# Connectors.net
KiCad netlist of a schematic drawn in Altium Designer
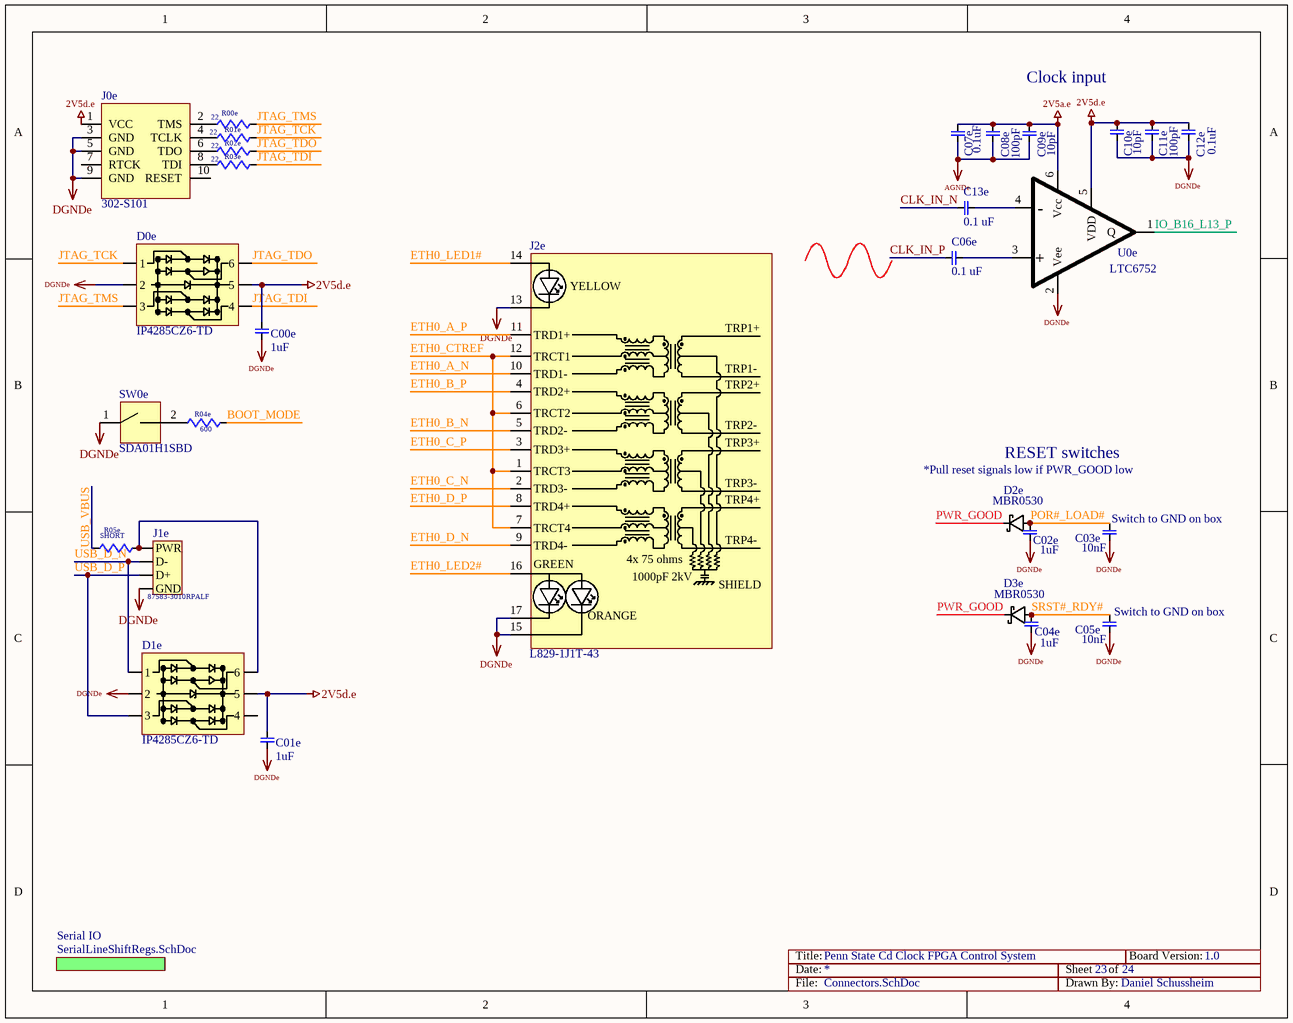
[diagram p0: Connectors.SchDoc]

(export (version "E")
  (design (tool "Eeschema 10.0.6"))
  (components
    (comp (ref "C00e")
      (value "1uF")
      (footprint "0603")
      (libsource (lib "Mercury_AD_BaseBoard_SCHLIB") (part "CAP"))
    )
    (comp (ref "C01e")
      (value "1uF")
      (footprint "0603")
      (libsource (lib "Mercury_AD_BaseBoard_SCHLIB") (part "CAP"))
    )
    (comp (ref "C02e")
      (value "1uF")
      (footprint "0603")
      (libsource (lib "Mercury_AD_BaseBoard_SCHLIB") (part "CAP"))
    )
    (comp (ref "C03e")
      (value "10nF")
      (footprint "0603")
      (libsource (lib "Mercury_AD_BaseBoard_SCHLIB") (part "CAP"))
    )
    (comp (ref "C04e")
      (value "1uF")
      (footprint "0603")
      (libsource (lib "Mercury_AD_BaseBoard_SCHLIB") (part "CAP"))
    )
    (comp (ref "C05e")
      (value "10nF")
      (footprint "0603")
      (libsource (lib "Mercury_AD_BaseBoard_SCHLIB") (part "CAP"))
    )
    (comp (ref "C06e") (value "0.1 uF") (footprint "0805") (libsource (lib "") (part "CAP_1")))
    (comp (ref "C07e")
      (value "0.1uF")
      (footprint "0603")
      (libsource (lib "Mercury_AD_BaseBoard_SCHLIB") (part "CAP"))
    )
    (comp (ref "C08e")
      (value "100pF")
      (footprint "0603")
      (libsource (lib "Mercury_AD_BaseBoard_SCHLIB") (part "CAP"))
    )
    (comp (ref "C09e")
      (value "10pF")
      (footprint "0603")
      (libsource (lib "Mercury_AD_BaseBoard_SCHLIB") (part "CAP"))
    )
    (comp (ref "C10e")
      (value "10pF")
      (footprint "0603")
      (libsource (lib "Mercury_AD_BaseBoard_SCHLIB") (part "CAP"))
    )
    (comp (ref "C11e")
      (value "100pF")
      (footprint "0603")
      (libsource (lib "Mercury_AD_BaseBoard_SCHLIB") (part "CAP"))
    )
    (comp (ref "C12e")
      (value "0.1uF")
      (footprint "0603")
      (libsource (lib "Mercury_AD_BaseBoard_SCHLIB") (part "CAP"))
    )
    (comp (ref "C13e") (value "0.1 uF") (footprint "0805") (libsource (lib "") (part "CAP_1")))
    (comp (ref "D0e")
      (value "IP4285CZ6-TD")
      (footprint "6-TSOP")
      (libsource (lib "Mercury_AD_BaseBoard_SCHLIB") (part "IP4285CZ6-TD"))
    )
    (comp (ref "D1e")
      (value "IP4285CZ6-TD")
      (footprint "6-TSOP")
      (libsource (lib "Mercury_AD_BaseBoard_SCHLIB") (part "IP4285CZ6-TD"))
    )
    (comp (ref "D2e")
      (value "MBR0530")
      (footprint "SOD123")
      (libsource (lib "Mercury_AD_BaseBoard_SCHLIB") (part "Schottky_Diode"))
    )
    (comp (ref "D3e")
      (value "MBR0530")
      (footprint "SOD123")
      (libsource (lib "Mercury_AD_BaseBoard_SCHLIB") (part "Schottky_Diode"))
    )
    (comp (ref "J0e")
      (value "302-S101")
      (footprint "3020-10-0300-00")
      (description "JTAG Connector")
      (libsource (lib "Mercury_AD_BaseBoard_SCHLIB") (part "JTAG_10"))
    )
    (comp (ref "J1e")
      (value "87583-3010RPALF")
      (footprint "87583-3010RPALF")
      (libsource (lib "Mercury_AD_BaseBoard_SCHLIB") (part "87583-3010RPALF"))
    )
    (comp (ref "J2e")
      (value "L829-1J1T-43")
      (footprint "L829-1J1T-43")
      (libsource (lib "Mercury_AD_BaseBoard_SCHLIB") (part "L829-1J1T-43"))
    )
    (comp (ref "R00e")
      (value "22")
      (footprint "0603")
      (libsource (lib "Mercury_AD_BaseBoard_SCHLIB") (part "RES"))
    )
    (comp (ref "R01e")
      (value "22")
      (footprint "0603")
      (libsource (lib "Mercury_AD_BaseBoard_SCHLIB") (part "RES"))
    )
    (comp (ref "R02e")
      (value "22")
      (footprint "0603")
      (libsource (lib "Mercury_AD_BaseBoard_SCHLIB") (part "RES"))
    )
    (comp (ref "R03e")
      (value "22")
      (footprint "0603")
      (libsource (lib "Mercury_AD_BaseBoard_SCHLIB") (part "RES"))
    )
    (comp (ref "R04e")
      (value "600")
      (footprint "0603")
      (libsource (lib "Mercury_AD_BaseBoard_SCHLIB") (part "RES"))
    )
    (comp (ref "R05e")
      (value "SHORT")
      (footprint "0603")
      (libsource (lib "Mercury_AD_BaseBoard_SCHLIB") (part "RES"))
    )
    (comp (ref "SW0e")
      (value "SDA01H1SBD")
      (footprint "SDA01H1SBD")
      (libsource (lib "Mercury_AD_BaseBoard_SCHLIB") (part "SW1"))
    )
    (comp (ref "U0e")
      (value "LTC6752")
      (footprint "sc70")
      (libsource (lib "Mercury_AD_BaseBoard_SCHLIB") (part "LTC6752"))
    )
  )
  (nets
    (net (code "1") (name "/BOOT_MODE") (class "Default") (node (ref "R04e") (pin "2") (pintype "passive")))
    (net (code "2") (name "/CLK_IN_N") (class "Default") (node (ref "C13e") (pin "1") (pintype "passive")))
    (net (code "3") (name "/CLK_IN_P") (class "Default") (node (ref "C06e") (pin "1") (pintype "passive")))
    (net (code "4") (name "/ETH0_A_N") (class "Default")
      (node (ref "J2e") (pin "10") (pinfunction "TRD1-_10") (pintype "passive"))
    )
    (net (code "5") (name "/ETH0_A_P") (class "Default")
      (node (ref "J2e") (pin "11") (pinfunction "TRD1+_11") (pintype "passive"))
    )
    (net (code "6") (name "/ETH0_B_N") (class "Default")
      (node (ref "J2e") (pin "5") (pinfunction "TRD2-_5") (pintype "passive"))
    )
    (net (code "7") (name "/ETH0_B_P") (class "Default")
      (node (ref "J2e") (pin "4") (pinfunction "TRD2+_4") (pintype "passive"))
    )
    (net (code "8") (name "/ETH0_CTREF") (class "Default")
      (node (ref "J2e") (pin "1") (pinfunction "TRCT3_1") (pintype "passive"))
      (node (ref "J2e") (pin "12") (pinfunction "TRCT1_12") (pintype "passive"))
      (node (ref "J2e") (pin "6") (pinfunction "TRCT2_6") (pintype "passive"))
      (node (ref "J2e") (pin "7") (pinfunction "TRCT4_7") (pintype "passive"))
    )
    (net (code "9") (name "/ETH0_C_N") (class "Default")
      (node (ref "J2e") (pin "2") (pinfunction "TRD3-_2") (pintype "passive"))
    )
    (net (code "10") (name "/ETH0_C_P") (class "Default")
      (node (ref "J2e") (pin "3") (pinfunction "TRD3+_3") (pintype "passive"))
    )
    (net (code "11") (name "/ETH0_D_N") (class "Default")
      (node (ref "J2e") (pin "9") (pinfunction "TRD4-_9") (pintype "passive"))
    )
    (net (code "12") (name "/ETH0_D_P") (class "Default")
      (node (ref "J2e") (pin "8") (pinfunction "TRD4+_8") (pintype "passive"))
    )
    (net (code "13") (name "/ETH0_LED1#") (class "Default") (node (ref "J2e") (pin "14") (pintype "passive")))
    (net (code "14") (name "/ETH0_LED2#") (class "Default") (node (ref "J2e") (pin "16") (pintype "passive")))
    (net (code "15") (name "/IO_B16_L13_P") (class "Default")
      (node (ref "U0e") (pin "1") (pinfunction "Q_1") (pintype "passive"))
    )
    (net (code "16") (name "/JTAG_TCK") (class "Default")
      (node (ref "D0e") (pin "1") (pinfunction "1_1") (pintype "passive"))
      (node (ref "R01e") (pin "2") (pintype "passive"))
    )
    (net (code "17") (name "/JTAG_TDI") (class "Default")
      (node (ref "D0e") (pin "4") (pinfunction "4_4") (pintype "passive"))
      (node (ref "R03e") (pin "2") (pintype "passive"))
    )
    (net (code "18") (name "/JTAG_TDO") (class "Default")
      (node (ref "D0e") (pin "6") (pinfunction "6_6") (pintype "passive"))
      (node (ref "R02e") (pin "2") (pintype "passive"))
    )
    (net (code "19") (name "/JTAG_TMS") (class "Default")
      (node (ref "D0e") (pin "3") (pinfunction "3_3") (pintype "passive"))
      (node (ref "R00e") (pin "1") (pintype "passive"))
    )
    (net (code "20") (name "/POR#_LOAD#") (class "Default")
      (node (ref "C02e") (pin "1") (pintype "passive"))
      (node (ref "C03e") (pin "1") (pintype "passive"))
      (node (ref "D2e") (pin "2") (pinfunction "2_2") (pintype "passive"))
    )
    (net (code "21") (name "/PWR_GOOD") (class "Default")
      (node (ref "D2e") (pin "1") (pinfunction "1_1") (pintype "passive"))
      (node (ref "D3e") (pin "1") (pinfunction "1_1") (pintype "passive"))
    )
    (net (code "22") (name "/SRST#_RDY#") (class "Default")
      (node (ref "C04e") (pin "1") (pintype "passive"))
      (node (ref "C05e") (pin "1") (pintype "passive"))
      (node (ref "D3e") (pin "2") (pinfunction "2_2") (pintype "passive"))
    )
    (net (code "23") (name "/USB_D_N") (class "Default")
      (node (ref "D1e") (pin "1") (pinfunction "1_1") (pintype "passive"))
      (node (ref "J1e") (pin "D-") (pinfunction "D-_D-") (pintype "passive"))
    )
    (net (code "24") (name "/USB_D_P") (class "Default")
      (node (ref "D1e") (pin "3") (pinfunction "3_3") (pintype "passive"))
      (node (ref "J1e") (pin "D+") (pinfunction "D+_D+") (pintype "passive"))
    )
    (net (code "25") (name "/USB_VBUS") (class "Default") (node (ref "R05e") (pin "1") (pintype "passive")))
    (net (code "26") (name "2V5a.e") (class "Default")
      (node (ref "C07e") (pin "1") (pintype "passive"))
      (node (ref "C08e") (pin "1") (pintype "passive"))
      (node (ref "C09e") (pin "1") (pintype "passive"))
      (node (ref "U0e") (pin "6") (pinfunction "Vcc_6") (pintype "passive"))
    )
    (net (code "27") (name "2V5d.e") (class "Default")
      (node (ref "C00e") (pin "1") (pintype "passive"))
      (node (ref "C01e") (pin "1") (pintype "passive"))
      (node (ref "C10e") (pin "1") (pintype "passive"))
      (node (ref "C11e") (pin "1") (pintype "passive"))
      (node (ref "C12e") (pin "1") (pintype "passive"))
      (node (ref "D0e") (pin "5") (pinfunction "5_5") (pintype "passive"))
      (node (ref "D1e") (pin "5") (pinfunction "5_5") (pintype "passive"))
      (node (ref "J0e") (pin "1") (pinfunction "VCC_1") (pintype "passive"))
      (node (ref "U0e") (pin "5") (pinfunction "VDD_5") (pintype "passive"))
    )
    (net (code "28") (name "AGNDe") (class "Default")
      (node (ref "C07e") (pin "2") (pintype "passive"))
      (node (ref "C08e") (pin "2") (pintype "passive"))
      (node (ref "C09e") (pin "2") (pintype "passive"))
    )
    (net (code "29") (name "DGNDe") (class "Default")
      (node (ref "C00e") (pin "2") (pintype "passive"))
      (node (ref "C01e") (pin "2") (pintype "passive"))
      (node (ref "C02e") (pin "2") (pintype "passive"))
      (node (ref "C03e") (pin "2") (pintype "passive"))
      (node (ref "C04e") (pin "2") (pintype "passive"))
      (node (ref "C05e") (pin "2") (pintype "passive"))
      (node (ref "C10e") (pin "2") (pintype "passive"))
      (node (ref "C11e") (pin "2") (pintype "passive"))
      (node (ref "C12e") (pin "2") (pintype "passive"))
      (node (ref "D0e") (pin "2") (pinfunction "2_2") (pintype "passive"))
      (node (ref "D1e") (pin "2") (pinfunction "2_2") (pintype "passive"))
      (node (ref "J0e") (pin "3") (pinfunction "GND_3") (pintype "passive"))
      (node (ref "J0e") (pin "5") (pinfunction "GND_5") (pintype "passive"))
      (node (ref "J0e") (pin "9") (pinfunction "GND_9") (pintype "passive"))
      (node (ref "J1e") (pin "GND") (pinfunction "GND_GND") (pintype "passive"))
      (node (ref "J2e") (pin "13") (pintype "passive"))
      (node (ref "J2e") (pin "15") (pintype "passive"))
      (node (ref "J2e") (pin "17") (pintype "passive"))
      (node (ref "SW0e") (pin "1") (pinfunction "1_1") (pintype "passive"))
      (node (ref "U0e") (pin "2") (pinfunction "Vee_2") (pintype "passive"))
    )
    (net (code "30") (name "Net-(D1e-Pad6)") (class "Default")
      (node (ref "D1e") (pin "6") (pinfunction "6_6") (pintype "passive"))
      (node (ref "J1e") (pin "PWR") (pinfunction "PWR_PWR") (pintype "passive"))
      (node (ref "R05e") (pin "2") (pintype "passive"))
    )
    (net (code "31") (name "Net-(J0e-TCLK)") (class "Default")
      (node (ref "J0e") (pin "4") (pinfunction "TCLK_4") (pintype "passive"))
      (node (ref "R01e") (pin "1") (pintype "passive"))
    )
    (net (code "32") (name "Net-(J0e-TDI)") (class "Default")
      (node (ref "J0e") (pin "8") (pinfunction "TDI_8") (pintype "passive"))
      (node (ref "R03e") (pin "1") (pintype "passive"))
    )
    (net (code "33") (name "Net-(J0e-TDO)") (class "Default")
      (node (ref "J0e") (pin "6") (pinfunction "TDO_6") (pintype "passive"))
      (node (ref "R02e") (pin "1") (pintype "passive"))
    )
    (net (code "34") (name "Net-(J0e-TMS)") (class "Default")
      (node (ref "J0e") (pin "2") (pinfunction "TMS_2") (pintype "passive"))
      (node (ref "R00e") (pin "2") (pintype "passive"))
    )
    (net (code "35") (name "Net-(R04e-Pad1)") (class "Default")
      (node (ref "R04e") (pin "1") (pintype "passive"))
      (node (ref "SW0e") (pin "2") (pinfunction "2_2") (pintype "passive"))
    )
    (net (code "36") (name "Net-(U0e-+)") (class "Default")
      (node (ref "C06e") (pin "2") (pintype "passive"))
      (node (ref "U0e") (pin "3") (pinfunction "+_3") (pintype "passive"))
    )
    (net (code "37") (name "Net-(U0e--)") (class "Default")
      (node (ref "C13e") (pin "2") (pintype "passive"))
      (node (ref "U0e") (pin "4") (pinfunction "-_4") (pintype "passive"))
    )
    (net (code "38") (name "unconnected-(D1e-Pad4)") (class "Default")
      (node (ref "D1e") (pin "4") (pinfunction "4_4") (pintype "passive"))
    )
    (net (code "39") (name "unconnected-(J0e-RESET-Pad10)") (class "Default")
      (node (ref "J0e") (pin "10") (pinfunction "RESET_10") (pintype "passive"))
    )
    (net (code "40") (name "unconnected-(J0e-RTCK-Pad7)") (class "Default")
      (node (ref "J0e") (pin "7") (pinfunction "RTCK_7") (pintype "passive"))
    )
  )
)
